# CH9141_Bluetooth.net
KiCad netlist of a schematic drawn in EAGLE
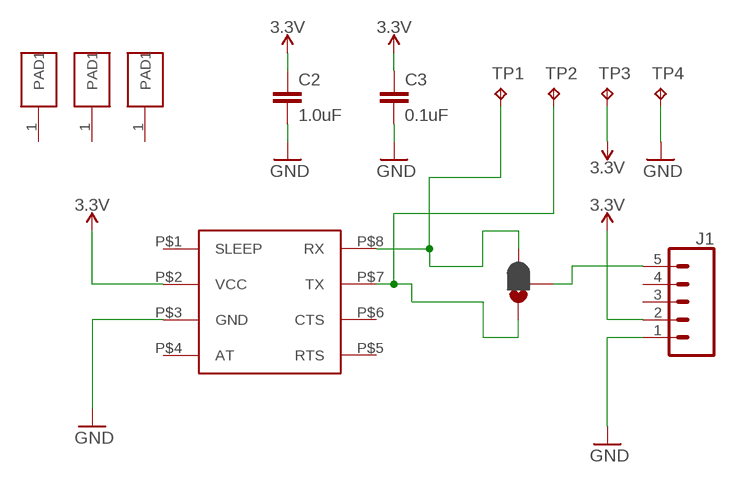
[diagram p0: schematic, sheet 1]

(export (version "E")
  (design (tool "Eeschema 10.0.6"))
  (components
    (comp (ref "C2")
      (value "1.0uF")
      (footprint "eagle-import:0805")
      (libsource (lib "eagle-import") (part "1.0UF-0805-25V-10%"))
    )
    (comp (ref "C3")
      (value "0.1uF")
      (footprint "eagle-import:0805")
      (libsource (lib "eagle-import") (part "CAP0805"))
    )
    (comp (ref "J1")
      (value "CONN_051.27MM")
      (footprint "eagle-import:1X05_1.27MM")
      (libsource (lib "eagle-import") (part "CONN_051.27MM"))
    )
    (comp (ref "JP1")
      (value "JUMPER-SMT_3_1-NC_PASTE_NO-SILK")
      (footprint "eagle-import:SMT-JUMPER_3_1-NC_PASTE_NO-SILK")
      (libsource (lib "eagle-import") (part "JUMPER-SMT_3_1-NC_PASTE_NO-SILK"))
    )
    (comp (ref "TP1")
      (value "TPB2,54")
      (footprint "eagle-import:B2,54")
      (libsource (lib "eagle-import") (part "TPB2,54"))
    )
    (comp (ref "TP2")
      (value "TPB2,54")
      (footprint "eagle-import:B2,54")
      (libsource (lib "eagle-import") (part "TPB2,54"))
    )
    (comp (ref "TP3")
      (value "TPB2,54")
      (footprint "eagle-import:B2,54")
      (libsource (lib "eagle-import") (part "TPB2,54"))
    )
    (comp (ref "TP4")
      (value "TPB2,54")
      (footprint "eagle-import:B2,54")
      (libsource (lib "eagle-import") (part "TPB2,54"))
    )
    (comp (ref "U$1")
      (value "CH9141")
      (footprint "eagle-import:CH9141_FOOTPRINT")
      (libsource (lib "eagle-import") (part "CH9141"))
    )
    (comp (ref "U$2")
      (value "SINGLE_1.27MM_HOLE")
      (footprint "eagle-import:1.27MM_SINGLE_HOLE")
      (libsource (lib "eagle-import") (part "SINGLE_1.27MM_HOLE"))
    )
    (comp (ref "U$3")
      (value "SINGLE_1.27MM_HOLE")
      (footprint "eagle-import:1.27MM_SINGLE_HOLE")
      (libsource (lib "eagle-import") (part "SINGLE_1.27MM_HOLE"))
    )
    (comp (ref "U$4")
      (value "SINGLE_1.27MM_HOLE")
      (footprint "eagle-import:1.27MM_SINGLE_HOLE")
      (libsource (lib "eagle-import") (part "SINGLE_1.27MM_HOLE"))
    )
  )
  (nets
    (net (code "1") (name "3.3V") (class "Default")
      (node (ref "C2") (pin "1") (pinfunction "1_1") (pintype "passive"))
      (node (ref "C3") (pin "1") (pinfunction "1_1") (pintype "passive"))
      (node (ref "J1") (pin "2") (pinfunction "2_2") (pintype "passive"))
      (node (ref "TP3") (pin "TP") (pinfunction "TP_TP") (pintype "input"))
      (node (ref "U$1") (pin "P$2") (pinfunction "VCC_P$2") (pintype "bidirectional"))
    )
    (net (code "2") (name "GND") (class "Default")
      (node (ref "C2") (pin "2") (pinfunction "2_2") (pintype "passive"))
      (node (ref "C3") (pin "2") (pinfunction "2_2") (pintype "passive"))
      (node (ref "J1") (pin "1") (pinfunction "1_1") (pintype "passive"))
      (node (ref "TP4") (pin "TP") (pinfunction "TP_TP") (pintype "input"))
      (node (ref "U$1") (pin "P$3") (pinfunction "GND_P$3") (pintype "bidirectional"))
    )
    (net (code "3") (name "Net-(J1-Pad5)") (class "Default")
      (node (ref "J1") (pin "5") (pinfunction "5_5") (pintype "passive"))
      (node (ref "JP1") (pin "2") (pinfunction "2_2") (pintype "passive"))
    )
    (net (code "4") (name "Net-(U$1-RX)") (class "Default")
      (node (ref "JP1") (pin "3") (pinfunction "3_3") (pintype "passive"))
      (node (ref "TP1") (pin "TP") (pinfunction "TP_TP") (pintype "input"))
      (node (ref "U$1") (pin "P$8") (pinfunction "RX_P$8") (pintype "bidirectional"))
    )
    (net (code "5") (name "Net-(U$1-TX)") (class "Default")
      (node (ref "JP1") (pin "1") (pinfunction "1_1") (pintype "passive"))
      (node (ref "TP2") (pin "TP") (pinfunction "TP_TP") (pintype "input"))
      (node (ref "U$1") (pin "P$7") (pinfunction "TX_P$7") (pintype "bidirectional"))
    )
    (net (code "6") (name "unconnected-(J1-Pad3)") (class "Default")
      (node (ref "J1") (pin "3") (pinfunction "3_3") (pintype "passive"))
    )
    (net (code "7") (name "unconnected-(J1-Pad4)") (class "Default")
      (node (ref "J1") (pin "4") (pinfunction "4_4") (pintype "passive"))
    )
    (net (code "8") (name "unconnected-(U$1-AT-PadP$4)") (class "Default")
      (node (ref "U$1") (pin "P$4") (pinfunction "AT_P$4") (pintype "bidirectional"))
    )
    (net (code "9") (name "unconnected-(U$1-CTS-PadP$6)") (class "Default")
      (node (ref "U$1") (pin "P$6") (pinfunction "CTS_P$6") (pintype "bidirectional"))
    )
    (net (code "10") (name "unconnected-(U$1-RTS-PadP$5)") (class "Default")
      (node (ref "U$1") (pin "P$5") (pinfunction "RTS_P$5") (pintype "bidirectional"))
    )
    (net (code "11") (name "unconnected-(U$1-SLEEP-PadP$1)") (class "Default")
      (node (ref "U$1") (pin "P$1") (pinfunction "SLEEP_P$1") (pintype "bidirectional"))
    )
    (net (code "12") (name "unconnected-(U$2-PAD1-Pad1)") (class "Default")
      (node (ref "U$2") (pin "1") (pinfunction "PAD1_1") (pintype "bidirectional"))
    )
    (net (code "13") (name "unconnected-(U$3-PAD1-Pad1)") (class "Default")
      (node (ref "U$3") (pin "1") (pinfunction "PAD1_1") (pintype "bidirectional"))
    )
    (net (code "14") (name "unconnected-(U$4-PAD1-Pad1)") (class "Default")
      (node (ref "U$4") (pin "1") (pinfunction "PAD1_1") (pintype "bidirectional"))
    )
  )
)
